# MicroSD_Card.net
KiCad netlist of a schematic drawn in Altium Designer
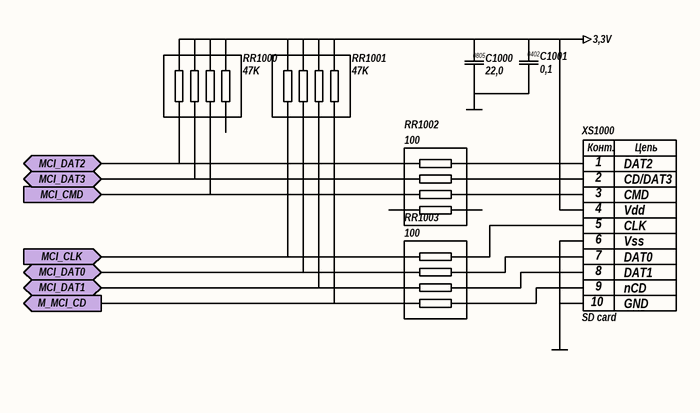
[diagram p0: MicroSD Card.SchDoc]

(export (version "E")
  (design (tool "Eeschema 10.0.6"))
  (components
    (comp (ref "C1000")
      (value "22,0")
      (footprint "CAP0805")
      (description "Конденсатор чип")
      (libsource (lib "EwgPassive") (part "CAP_0805"))
    )
    (comp (ref "C1001")
      (value "0,1")
      (footprint "CAP0402")
      (description "Конденсатор чип")
      (libsource (lib "EwgPassive") (part "CAP_0402"))
    )
    (comp (ref "RR1000")
      (value "47K")
      (footprint "CAY16")
      (description "Сборка резисторная")
      (libsource (lib "EwgPassive") (part "RESASM_CAY16"))
    )
    (comp (ref "RR1001")
      (value "47K")
      (footprint "CAY16")
      (description "Сборка резисторная")
      (libsource (lib "EwgPassive") (part "RESASM_CAY16"))
    )
    (comp (ref "RR1002")
      (value "100")
      (footprint "CAY16")
      (description "Сборка резисторная")
      (libsource (lib "EwgPassive") (part "RESASM_CAY16"))
    )
    (comp (ref "RR1003")
      (value "100")
      (footprint "CAY16")
      (description "Сборка резисторная")
      (libsource (lib "EwgPassive") (part "RESASM_CAY16"))
    )
    (comp (ref "XS1000")
      (value "SD card")
      (footprint "112J-TDAR-R-SDCARD")
      (description "Слот MMC")
      (libsource (lib "EwgConnectors") (part "112J-TDAR-R-SDCARD"))
    )
  )
  (nets
    (net (code "1") (name "/MCI_CLK") (class "Default")
      (node (ref "RR1001") (pin "4") (pinfunction "4_4") (pintype "passive"))
      (node (ref "RR1003") (pin "1") (pinfunction "1_1") (pintype "passive"))
    )
    (net (code "2") (name "/MCI_CMD") (class "Default")
      (node (ref "RR1000") (pin "2") (pinfunction "2_2") (pintype "passive"))
      (node (ref "RR1002") (pin "3") (pinfunction "3_3") (pintype "passive"))
    )
    (net (code "3") (name "/MCI_DAT0") (class "Default")
      (node (ref "RR1001") (pin "3") (pinfunction "3_3") (pintype "passive"))
      (node (ref "RR1003") (pin "2") (pinfunction "2_2") (pintype "passive"))
    )
    (net (code "4") (name "/MCI_DAT1") (class "Default")
      (node (ref "RR1001") (pin "2") (pinfunction "2_2") (pintype "passive"))
      (node (ref "RR1003") (pin "3") (pinfunction "3_3") (pintype "passive"))
    )
    (net (code "5") (name "/MCI_DAT2") (class "Default")
      (node (ref "RR1000") (pin "4") (pinfunction "4_4") (pintype "passive"))
      (node (ref "RR1002") (pin "1") (pinfunction "1_1") (pintype "passive"))
    )
    (net (code "6") (name "/MCI_DAT3") (class "Default")
      (node (ref "RR1000") (pin "3") (pinfunction "3_3") (pintype "passive"))
      (node (ref "RR1002") (pin "2") (pinfunction "2_2") (pintype "passive"))
    )
    (net (code "7") (name "/M_MCI_CD") (class "Default")
      (node (ref "RR1001") (pin "1") (pinfunction "1_1") (pintype "passive"))
      (node (ref "RR1003") (pin "4") (pinfunction "4_4") (pintype "passive"))
    )
    (net (code "8") (name "3,3V") (class "Default")
      (node (ref "C1000") (pin "1") (pintype "passive"))
      (node (ref "C1001") (pin "1") (pintype "passive"))
      (node (ref "RR1000") (pin "5") (pinfunction "5_5") (pintype "passive"))
      (node (ref "RR1000") (pin "6") (pinfunction "6_6") (pintype "passive"))
      (node (ref "RR1000") (pin "7") (pinfunction "7_7") (pintype "passive"))
      (node (ref "RR1000") (pin "8") (pinfunction "8_8") (pintype "passive"))
      (node (ref "RR1001") (pin "5") (pinfunction "5_5") (pintype "passive"))
      (node (ref "RR1001") (pin "6") (pinfunction "6_6") (pintype "passive"))
      (node (ref "RR1001") (pin "7") (pinfunction "7_7") (pintype "passive"))
      (node (ref "RR1001") (pin "8") (pinfunction "8_8") (pintype "passive"))
      (node (ref "XS1000") (pin "4") (pinfunction "Vdd_4") (pintype "passive"))
    )
    (net (code "9") (name "GND") (class "Default")
      (node (ref "C1000") (pin "2") (pintype "passive"))
      (node (ref "C1001") (pin "2") (pintype "passive"))
      (node (ref "XS1000") (pin "10") (pinfunction "GND_10") (pintype "passive"))
      (node (ref "XS1000") (pin "6") (pinfunction "Vss_6") (pintype "passive"))
    )
    (net (code "10") (name "Net-(XS1000-CD{slash}DAT3)") (class "Default")
      (node (ref "RR1002") (pin "7") (pinfunction "7_7") (pintype "passive"))
      (node (ref "XS1000") (pin "2") (pinfunction "CD/DAT3_2") (pintype "passive"))
    )
    (net (code "11") (name "Net-(XS1000-CLK)") (class "Default")
      (node (ref "RR1003") (pin "8") (pinfunction "8_8") (pintype "passive"))
      (node (ref "XS1000") (pin "5") (pinfunction "CLK_5") (pintype "passive"))
    )
    (net (code "12") (name "Net-(XS1000-CMD)") (class "Default")
      (node (ref "RR1002") (pin "6") (pinfunction "6_6") (pintype "passive"))
      (node (ref "XS1000") (pin "3") (pinfunction "CMD_3") (pintype "passive"))
    )
    (net (code "13") (name "Net-(XS1000-DAT0)") (class "Default")
      (node (ref "RR1003") (pin "7") (pinfunction "7_7") (pintype "passive"))
      (node (ref "XS1000") (pin "7") (pinfunction "DAT0_7") (pintype "passive"))
    )
    (net (code "14") (name "Net-(XS1000-DAT1)") (class "Default")
      (node (ref "RR1003") (pin "6") (pinfunction "6_6") (pintype "passive"))
      (node (ref "XS1000") (pin "8") (pinfunction "DAT1_8") (pintype "passive"))
    )
    (net (code "15") (name "Net-(XS1000-DAT2)") (class "Default")
      (node (ref "RR1002") (pin "8") (pinfunction "8_8") (pintype "passive"))
      (node (ref "XS1000") (pin "1") (pinfunction "DAT2_1") (pintype "passive"))
    )
    (net (code "16") (name "Net-(XS1000-nCD)") (class "Default")
      (node (ref "RR1003") (pin "5") (pinfunction "5_5") (pintype "passive"))
      (node (ref "XS1000") (pin "9") (pinfunction "nCD_9") (pintype "passive"))
    )
    (net (code "17") (name "unconnected-(RR1000-Pad1)") (class "Default")
      (node (ref "RR1000") (pin "1") (pinfunction "1_1") (pintype "passive"))
    )
    (net (code "18") (name "unconnected-(RR1002-Pad4)") (class "Default")
      (node (ref "RR1002") (pin "4") (pinfunction "4_4") (pintype "passive"))
    )
    (net (code "19") (name "unconnected-(RR1002-Pad5)") (class "Default")
      (node (ref "RR1002") (pin "5") (pinfunction "5_5") (pintype "passive"))
    )
  )
)
